# Sheet3.net
KiCad netlist of a schematic drawn in Altium Designer
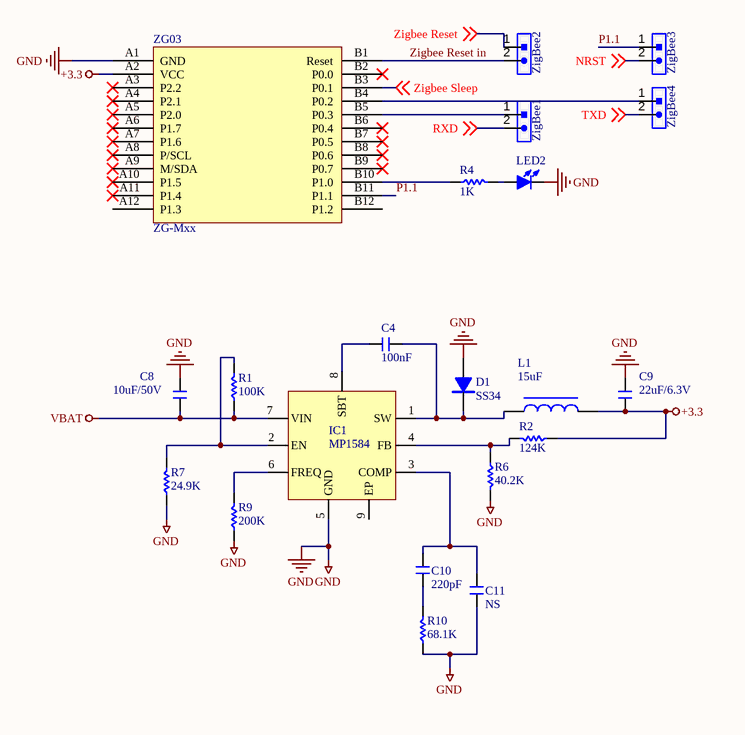
[diagram p0: Sheet3.SchDoc]

(export (version "E")
  (design (tool "Eeschema 10.0.6"))
  (components
    (comp (ref "C4")
      (value "100nF")
      (footprint "C 0402")
      (description "Non-polar patch capacitor")
      (fields (field (name "版权归属") "源创客"))
      (libsource (lib "Passive (Resistor-Capacitor-Inductor-Veristor-Ferrite)") (part "C"))
    )
    (comp (ref "C8")
      (value "10uF/50V")
      (footprint "C 1206")
      (description "Non-polar patch capacitor")
      (fields (field (name "版权归属") "源创客"))
      (libsource (lib "Passive (Resistor-Capacitor-Inductor-Veristor-Ferrite)") (part "C"))
    )
    (comp (ref "C9")
      (value "22uF/6.3V")
      (footprint "C 1206")
      (description "Non-polar patch capacitor")
      (fields (field (name "版权归属") "源创客"))
      (libsource (lib "Passive (Resistor-Capacitor-Inductor-Veristor-Ferrite)") (part "C"))
    )
    (comp (ref "C10")
      (value "220pF")
      (footprint "C 0402")
      (description "Non-polar patch capacitor")
      (fields (field (name "版权归属") "源创客"))
      (libsource (lib "Passive (Resistor-Capacitor-Inductor-Veristor-Ferrite)") (part "C"))
    )
    (comp (ref "C11")
      (value "NS")
      (footprint "C 0402")
      (description "Non-polar patch capacitor")
      (fields (field (name "版权归属") "源创客"))
      (libsource (lib "Passive (Resistor-Capacitor-Inductor-Veristor-Ferrite)") (part "C"))
    )
    (comp (ref "D1")
      (value "SS34")
      (footprint "SMA")
      (description "Schottky diodes")
      (fields (field (name "版权归属") "源创客"))
      (libsource (lib "Diode-Zener-Rectifier Bridge") (part "SS34"))
    )
    (comp (ref "IC1")
      (value "MP1584")
      (footprint "SOP8_N-EP")
      (description "DC step-down chip")
      (libsource (lib "Integrated Circuit") (part "MP1584"))
    )
    (comp (ref "L1")
      (value "15uF")
      (footprint "WHC0630")
      (description "One-piece high current inductor")
      (libsource (lib "Passive (Resistor-Capacitor-Inductor-Veristor-Ferrite)") (part "L-WHC"))
    )
    (comp (ref "LED2")
      (value "LED-SMD")
      (footprint "LED 0805B")
      (description "Patch LED")
      (fields (field (name "版权归属") "源创客"))
      (libsource (lib "LED") (part "LED-SMD"))
    )
    (comp (ref "R1")
      (value "100K")
      (footprint "R 0402-HP")
      (description "Chip resistor")
      (fields (field (name "版权归属") "源创客"))
      (libsource (lib "Passive (Resistor-Capacitor-Inductor-Veristor-Ferrite)") (part "R"))
    )
    (comp (ref "R2")
      (value "124K")
      (footprint "R 0402-HP")
      (description "Chip resistor")
      (fields (field (name "版权归属") "源创客"))
      (libsource (lib "Passive (Resistor-Capacitor-Inductor-Veristor-Ferrite)") (part "R"))
    )
    (comp (ref "R4")
      (value "1K")
      (footprint "R 0805")
      (description "Chip resistor")
      (fields (field (name "版权归属") "源创客"))
      (libsource (lib "Passive (Resistor-Capacitor-Inductor-Veristor-Ferrite)") (part "R"))
    )
    (comp (ref "R6")
      (value "40.2K")
      (footprint "R 0402-HP")
      (description "Chip resistor")
      (fields (field (name "版权归属") "源创客"))
      (libsource (lib "Passive (Resistor-Capacitor-Inductor-Veristor-Ferrite)") (part "R"))
    )
    (comp (ref "R7")
      (value "24.9K")
      (footprint "R 0402-HP")
      (description "Chip resistor")
      (fields (field (name "版权归属") "源创客"))
      (libsource (lib "Passive (Resistor-Capacitor-Inductor-Veristor-Ferrite)") (part "R"))
    )
    (comp (ref "R9")
      (value "200K")
      (footprint "R 0402-HP")
      (description "Chip resistor")
      (fields (field (name "版权归属") "源创客"))
      (libsource (lib "Passive (Resistor-Capacitor-Inductor-Veristor-Ferrite)") (part "R"))
    )
    (comp (ref "R10")
      (value "68.1K")
      (footprint "R 0402-HP")
      (description "Chip resistor")
      (fields (field (name "版权归属") "源创客"))
      (libsource (lib "Passive (Resistor-Capacitor-Inductor-Veristor-Ferrite)") (part "R"))
    )
    (comp (ref "ZG03") (value "ZG-Mxx") (footprint "XBee") (libsource (lib "XBee") (part "XBee")))
    (comp (ref "ZigBee1")
      (value "HDR-1X2")
      (footprint "HDR-1X2")
      (description "2P Connector")
      (fields (field (name "版权归属") "源创客"))
      (libsource (lib "Connectors") (part "Header 2"))
    )
    (comp (ref "ZigBee2")
      (value "HDR-1X2")
      (footprint "HDR-1X2")
      (description "2P Connector")
      (fields (field (name "版权归属") "源创客"))
      (libsource (lib "Connectors") (part "Header 2"))
    )
    (comp (ref "ZigBee3")
      (value "HDR-1X2")
      (footprint "HDR-1X2")
      (description "2P Connector")
      (fields (field (name "版权归属") "源创客"))
      (libsource (lib "Connectors") (part "Header 2"))
    )
    (comp (ref "ZigBee4")
      (value "HDR-1X2")
      (footprint "HDR-1X2")
      (description "2P Connector")
      (fields (field (name "版权归属") "源创客"))
      (libsource (lib "Connectors") (part "Header 2"))
    )
  )
  (nets
    (net (code "1") (name "+3.3") (class "Default")
      (node (ref "C9") (pin "1") (pinfunction "1_1") (pintype "passive"))
      (node (ref "L1") (pin "2") (pinfunction "2_2") (pintype "passive"))
      (node (ref "R2") (pin "1") (pinfunction "1_1") (pintype "passive"))
      (node (ref "ZG03") (pin "A2") (pinfunction "VCC_A2") (pintype "passive"))
    )
    (net (code "3") (name "/P1.1") (class "Default")
      (node (ref "ZG03") (pin "B11") (pinfunction "P1.1_B11") (pintype "passive"))
      (node (ref "ZigBee3") (pin "1") (pintype "passive"))
    )
    (net (code "4") (name "/Zigbee Reset in") (class "Default")
      (node (ref "ZG03") (pin "B1") (pinfunction "Reset_B1") (pintype "passive"))
      (node (ref "ZigBee2") (pin "2") (pintype "passive"))
    )
    (net (code "5") (name "GND") (class "Default")
      (node (ref "C11") (pin "1") (pinfunction "1_1") (pintype "passive"))
      (node (ref "C8") (pin "2") (pinfunction "2_2") (pintype "passive"))
      (node (ref "C9") (pin "2") (pinfunction "2_2") (pintype "passive"))
      (node (ref "D1") (pin "1") (pinfunction "A_1") (pintype "passive"))
      (node (ref "IC1") (pin "5") (pinfunction "GND_5") (pintype "passive"))
      (node (ref "LED2") (pin "2") (pinfunction "K_2") (pintype "passive"))
      (node (ref "R10") (pin "1") (pinfunction "1_1") (pintype "passive"))
      (node (ref "R6") (pin "2") (pinfunction "2_2") (pintype "passive"))
      (node (ref "R7") (pin "1") (pinfunction "1_1") (pintype "passive"))
      (node (ref "R9") (pin "1") (pinfunction "1_1") (pintype "passive"))
      (node (ref "ZG03") (pin "A1") (pinfunction "GND_A1") (pintype "passive"))
    )
    (net (code "6") (name "NRST") (class "Default") (node (ref "ZigBee3") (pin "2") (pintype "passive")))
    (net (code "7") (name "Net-(C10-Pad1)") (class "Default")
      (node (ref "C10") (pin "1") (pinfunction "1_1") (pintype "passive"))
      (node (ref "R10") (pin "2") (pinfunction "2_2") (pintype "passive"))
    )
    (net (code "8") (name "Net-(D1-K)") (class "Default")
      (node (ref "C4") (pin "2") (pinfunction "2_2") (pintype "passive"))
      (node (ref "D1") (pin "2") (pinfunction "K_2") (pintype "passive"))
      (node (ref "IC1") (pin "1") (pinfunction "SW_1") (pintype "passive"))
      (node (ref "L1") (pin "1") (pinfunction "1_1") (pintype "passive"))
    )
    (net (code "9") (name "Net-(IC1-COMP)") (class "Default")
      (node (ref "C10") (pin "2") (pinfunction "2_2") (pintype "passive"))
      (node (ref "C11") (pin "2") (pinfunction "2_2") (pintype "passive"))
      (node (ref "IC1") (pin "3") (pinfunction "COMP_3") (pintype "passive"))
    )
    (net (code "10") (name "Net-(IC1-EN)") (class "Default")
      (node (ref "IC1") (pin "2") (pinfunction "EN_2") (pintype "passive"))
      (node (ref "R1") (pin "2") (pinfunction "2_2") (pintype "passive"))
      (node (ref "R7") (pin "2") (pinfunction "2_2") (pintype "passive"))
    )
    (net (code "11") (name "Net-(IC1-FB)") (class "Default")
      (node (ref "IC1") (pin "4") (pinfunction "FB_4") (pintype "passive"))
      (node (ref "R2") (pin "2") (pinfunction "2_2") (pintype "passive"))
      (node (ref "R6") (pin "1") (pinfunction "1_1") (pintype "passive"))
    )
    (net (code "12") (name "Net-(IC1-FREQ)") (class "Default")
      (node (ref "IC1") (pin "6") (pinfunction "FREQ_6") (pintype "passive"))
      (node (ref "R9") (pin "2") (pinfunction "2_2") (pintype "passive"))
    )
    (net (code "13") (name "Net-(IC1-SBT)") (class "Default")
      (node (ref "C4") (pin "1") (pinfunction "1_1") (pintype "passive"))
      (node (ref "IC1") (pin "8") (pinfunction "SBT_8") (pintype "passive"))
    )
    (net (code "14") (name "Net-(LED2-A)") (class "Default")
      (node (ref "LED2") (pin "1") (pinfunction "A_1") (pintype "passive"))
      (node (ref "R4") (pin "2") (pinfunction "2_2") (pintype "passive"))
    )
    (net (code "15") (name "Net-(ZG03-P0.2)") (class "Default")
      (node (ref "ZG03") (pin "B4") (pinfunction "P0.2_B4") (pintype "passive"))
      (node (ref "ZigBee4") (pin "1") (pintype "passive"))
    )
    (net (code "16") (name "Net-(ZG03-P0.3)") (class "Default")
      (node (ref "ZG03") (pin "B5") (pinfunction "P0.3_B5") (pintype "passive"))
      (node (ref "ZigBee1") (pin "1") (pintype "passive"))
    )
    (net (code "17") (name "Net-(ZG03-P1.0)") (class "Default")
      (node (ref "R4") (pin "1") (pinfunction "1_1") (pintype "passive"))
      (node (ref "ZG03") (pin "B10") (pinfunction "P1.0_B10") (pintype "passive"))
    )
    (net (code "18") (name "RXD") (class "Default") (node (ref "ZigBee1") (pin "2") (pintype "passive")))
    (net (code "19") (name "TXD") (class "Default") (node (ref "ZigBee4") (pin "2") (pintype "passive")))
    (net (code "20") (name "VBAT") (class "Default")
      (node (ref "C8") (pin "1") (pinfunction "1_1") (pintype "passive"))
      (node (ref "IC1") (pin "7") (pinfunction "VIN_7") (pintype "passive"))
      (node (ref "R1") (pin "1") (pinfunction "1_1") (pintype "passive"))
    )
    (net (code "21") (name "Zigbee Reset") (class "Default")
      (node (ref "ZigBee2") (pin "1") (pintype "passive"))
    )
    (net (code "22") (name "Zigbee Sleep") (class "Default")
      (node (ref "ZG03") (pin "B3") (pinfunction "P0.1_B3") (pintype "passive"))
    )
    (net (code "23") (name "unconnected-(IC1-EP-Pad9)") (class "Default")
      (node (ref "IC1") (pin "9") (pinfunction "EP_9") (pintype "passive"))
    )
    (net (code "24") (name "unconnected-(ZG03-M{slash}SDA-PadA9)") (class "Default")
      (node (ref "ZG03") (pin "A9") (pinfunction "M/SDA_A9") (pintype "passive+no_connect"))
    )
    (net (code "25") (name "unconnected-(ZG03-P0.0-PadB2)") (class "Default")
      (node (ref "ZG03") (pin "B2") (pinfunction "P0.0_B2") (pintype "passive+no_connect"))
    )
    (net (code "26") (name "unconnected-(ZG03-P0.4-PadB6)") (class "Default")
      (node (ref "ZG03") (pin "B6") (pinfunction "P0.4_B6") (pintype "passive+no_connect"))
    )
    (net (code "27") (name "unconnected-(ZG03-P0.5-PadB7)") (class "Default")
      (node (ref "ZG03") (pin "B7") (pinfunction "P0.5_B7") (pintype "passive+no_connect"))
    )
    (net (code "28") (name "unconnected-(ZG03-P0.6-PadB8)") (class "Default")
      (node (ref "ZG03") (pin "B8") (pinfunction "P0.6_B8") (pintype "passive+no_connect"))
    )
    (net (code "29") (name "unconnected-(ZG03-P0.7-PadB9)") (class "Default")
      (node (ref "ZG03") (pin "B9") (pinfunction "P0.7_B9") (pintype "passive+no_connect"))
    )
    (net (code "30") (name "unconnected-(ZG03-P1.2-PadB12)") (class "Default")
      (node (ref "ZG03") (pin "B12") (pinfunction "P1.2_B12") (pintype "passive"))
    )
    (net (code "31") (name "unconnected-(ZG03-P1.3-PadA12)") (class "Default")
      (node (ref "ZG03") (pin "A12") (pinfunction "P1.3_A12") (pintype "passive"))
    )
    (net (code "32") (name "unconnected-(ZG03-P1.4-PadA11)") (class "Default")
      (node (ref "ZG03") (pin "A11") (pinfunction "P1.4_A11") (pintype "passive+no_connect"))
    )
    (net (code "33") (name "unconnected-(ZG03-P1.5-PadA10)") (class "Default")
      (node (ref "ZG03") (pin "A10") (pinfunction "P1.5_A10") (pintype "passive+no_connect"))
    )
    (net (code "34") (name "unconnected-(ZG03-P1.6-PadA7)") (class "Default")
      (node (ref "ZG03") (pin "A7") (pinfunction "P1.6_A7") (pintype "passive+no_connect"))
    )
    (net (code "35") (name "unconnected-(ZG03-P1.7-PadA6)") (class "Default")
      (node (ref "ZG03") (pin "A6") (pinfunction "P1.7_A6") (pintype "passive+no_connect"))
    )
    (net (code "36") (name "unconnected-(ZG03-P2.0-PadA5)") (class "Default")
      (node (ref "ZG03") (pin "A5") (pinfunction "P2.0_A5") (pintype "passive+no_connect"))
    )
    (net (code "37") (name "unconnected-(ZG03-P2.1-PadA4)") (class "Default")
      (node (ref "ZG03") (pin "A4") (pinfunction "P2.1_A4") (pintype "passive+no_connect"))
    )
    (net (code "38") (name "unconnected-(ZG03-P2.2-PadA3)") (class "Default")
      (node (ref "ZG03") (pin "A3") (pinfunction "P2.2_A3") (pintype "passive+no_connect"))
    )
    (net (code "39") (name "unconnected-(ZG03-P{slash}SCL-PadA8)") (class "Default")
      (node (ref "ZG03") (pin "A8") (pinfunction "P/SCL_A8") (pintype "passive+no_connect"))
    )
  )
)
